# dual_switches.net
KiCad netlist of a schematic drawn in EAGLE
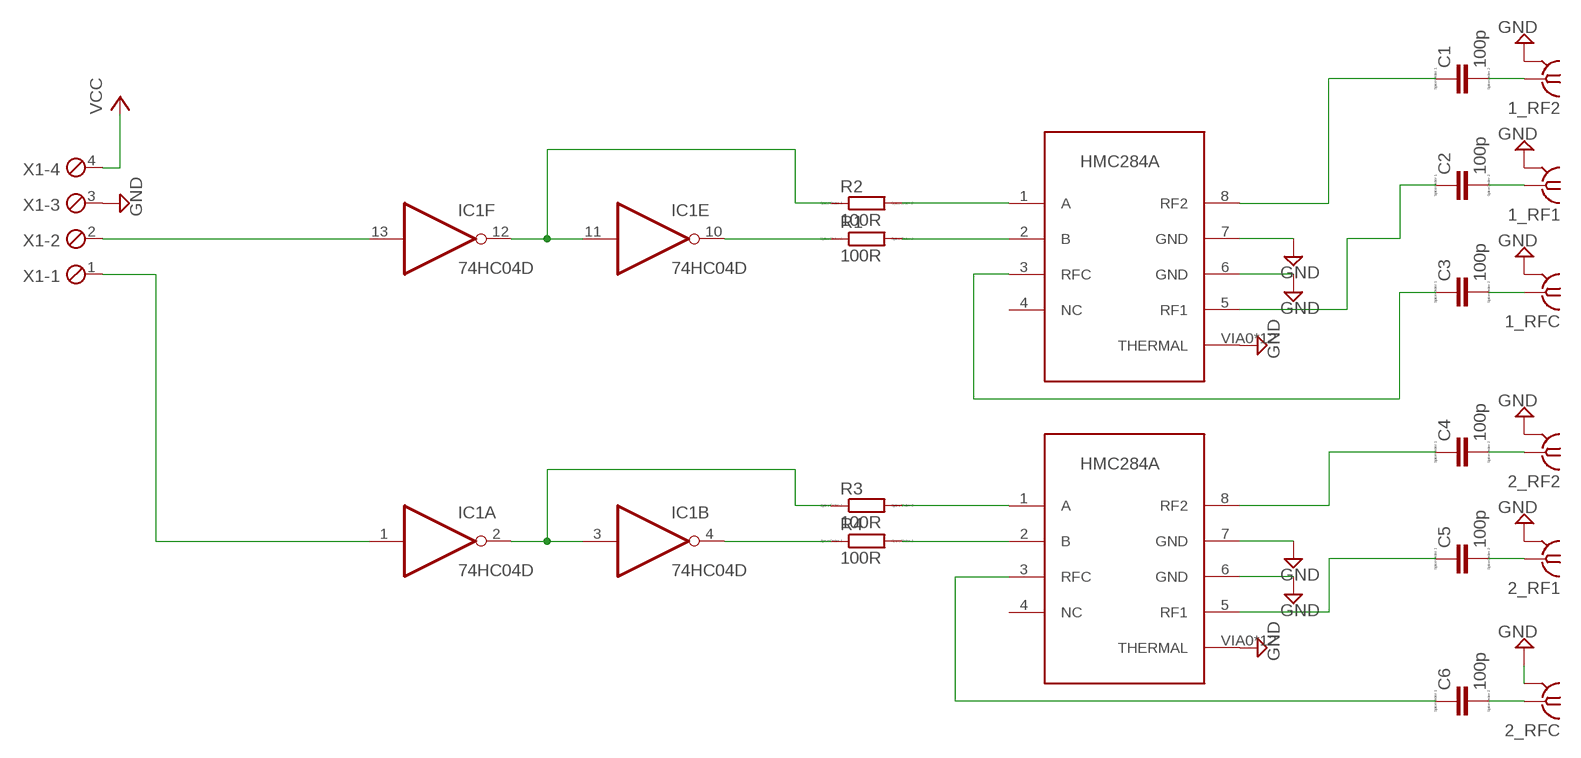
[diagram p0: schematic, sheet 1]

(export (version "E")
  (design (tool "Eeschema 10.0.6"))
  (components
    (comp (ref "1_RF1")
      (value "SMA-142-0701-801/806")
      (footprint "eagle-import:J502-ND-142-0701-801_806")
      (fields (field (name "MF") "JOHNSON COMPONENTS") (field (name "MPN") "142-0701-801"))
      (libsource (lib "eagle-import") (part "SMA-142-0701-801/806"))
    )
    (comp (ref "1_RF2")
      (value "SMA-142-0701-801/806")
      (footprint "eagle-import:J502-ND-142-0701-801_806")
      (fields (field (name "MF") "JOHNSON COMPONENTS") (field (name "MPN") "142-0701-801"))
      (libsource (lib "eagle-import") (part "SMA-142-0701-801/806"))
    )
    (comp (ref "1_RFC")
      (value "SMA-142-0701-801/806")
      (footprint "eagle-import:J502-ND-142-0701-801_806")
      (fields (field (name "MF") "JOHNSON COMPONENTS") (field (name "MPN") "142-0701-801"))
      (libsource (lib "eagle-import") (part "SMA-142-0701-801/806"))
    )
    (comp (ref "2_RF1")
      (value "SMA-142-0701-801/806")
      (footprint "eagle-import:J502-ND-142-0701-801_806")
      (fields (field (name "MF") "JOHNSON COMPONENTS") (field (name "MPN") "142-0701-801"))
      (libsource (lib "eagle-import") (part "SMA-142-0701-801/806"))
    )
    (comp (ref "2_RF2")
      (value "SMA-142-0701-801/806")
      (footprint "eagle-import:J502-ND-142-0701-801_806")
      (fields (field (name "MF") "JOHNSON COMPONENTS") (field (name "MPN") "142-0701-801"))
      (libsource (lib "eagle-import") (part "SMA-142-0701-801/806"))
    )
    (comp (ref "2_RFC")
      (value "SMA-142-0701-801/806")
      (footprint "eagle-import:J502-ND-142-0701-801_806")
      (fields (field (name "MF") "JOHNSON COMPONENTS") (field (name "MPN") "142-0701-801"))
      (libsource (lib "eagle-import") (part "SMA-142-0701-801/806"))
    )
    (comp (ref "C1")
      (value "100p")
      (footprint "eagle-import:C0402")
      (libsource (lib "eagle-import") (part "CC0402"))
    )
    (comp (ref "C2")
      (value "100p")
      (footprint "eagle-import:C0402")
      (libsource (lib "eagle-import") (part "CC0402"))
    )
    (comp (ref "C3")
      (value "100p")
      (footprint "eagle-import:C0402")
      (libsource (lib "eagle-import") (part "CC0402"))
    )
    (comp (ref "C4")
      (value "100p")
      (footprint "eagle-import:C0402")
      (libsource (lib "eagle-import") (part "CC0402"))
    )
    (comp (ref "C5")
      (value "100p")
      (footprint "eagle-import:C0402")
      (libsource (lib "eagle-import") (part "CC0402"))
    )
    (comp (ref "C6")
      (value "100p")
      (footprint "eagle-import:C0402")
      (libsource (lib "eagle-import") (part "CC0402"))
    )
    (comp (ref "IC1")
      (value "74HC04D")
      (footprint "eagle-import:SO14")
      (libsource (lib "eagle-import") (part "7404DHC"))
    )
    (comp (ref "R1")
      (value "100R")
      (footprint "eagle-import:R0603")
      (libsource (lib "eagle-import") (part "RR0603"))
    )
    (comp (ref "R2")
      (value "100R")
      (footprint "eagle-import:R0603")
      (libsource (lib "eagle-import") (part "RR0603"))
    )
    (comp (ref "R3")
      (value "100R")
      (footprint "eagle-import:R0603")
      (libsource (lib "eagle-import") (part "RR0603"))
    )
    (comp (ref "R4")
      (value "100R")
      (footprint "eagle-import:R0603")
      (libsource (lib "eagle-import") (part "RR0603"))
    )
    (comp (ref "U$1")
      (value "HMC284A")
      (footprint "eagle-import:MSOP-8G")
      (libsource (lib "eagle-import") (part "HMC284A"))
    )
    (comp (ref "U$2")
      (value "HMC284A")
      (footprint "eagle-import:MSOP-8G")
      (libsource (lib "eagle-import") (part "HMC284A"))
    )
    (comp (ref "X1")
      (value "MPT4")
      (footprint "eagle-import:4POL254")
      (libsource (lib "eagle-import") (part "MPT4"))
    )
  )
  (nets
    (net (code "1") (name "GND") (class "Default")
      (node (ref "1_RF1") (pin "G@1") (pinfunction "2_G@1") (pintype "passive"))
      (node (ref "1_RF1") (pin "G@2") (pinfunction "2_G@2") (pintype "passive"))
      (node (ref "1_RF1") (pin "G@3") (pinfunction "2_G@3") (pintype "passive"))
      (node (ref "1_RF1") (pin "G@4") (pinfunction "2_G@4") (pintype "passive"))
      (node (ref "1_RF2") (pin "G@1") (pinfunction "2_G@1") (pintype "passive"))
      (node (ref "1_RF2") (pin "G@2") (pinfunction "2_G@2") (pintype "passive"))
      (node (ref "1_RF2") (pin "G@3") (pinfunction "2_G@3") (pintype "passive"))
      (node (ref "1_RF2") (pin "G@4") (pinfunction "2_G@4") (pintype "passive"))
      (node (ref "1_RFC") (pin "G@1") (pinfunction "2_G@1") (pintype "passive"))
      (node (ref "1_RFC") (pin "G@2") (pinfunction "2_G@2") (pintype "passive"))
      (node (ref "1_RFC") (pin "G@3") (pinfunction "2_G@3") (pintype "passive"))
      (node (ref "1_RFC") (pin "G@4") (pinfunction "2_G@4") (pintype "passive"))
      (node (ref "2_RF1") (pin "G@1") (pinfunction "2_G@1") (pintype "passive"))
      (node (ref "2_RF1") (pin "G@2") (pinfunction "2_G@2") (pintype "passive"))
      (node (ref "2_RF1") (pin "G@3") (pinfunction "2_G@3") (pintype "passive"))
      (node (ref "2_RF1") (pin "G@4") (pinfunction "2_G@4") (pintype "passive"))
      (node (ref "2_RF2") (pin "G@1") (pinfunction "2_G@1") (pintype "passive"))
      (node (ref "2_RF2") (pin "G@2") (pinfunction "2_G@2") (pintype "passive"))
      (node (ref "2_RF2") (pin "G@3") (pinfunction "2_G@3") (pintype "passive"))
      (node (ref "2_RF2") (pin "G@4") (pinfunction "2_G@4") (pintype "passive"))
      (node (ref "2_RFC") (pin "G@1") (pinfunction "2_G@1") (pintype "passive"))
      (node (ref "2_RFC") (pin "G@2") (pinfunction "2_G@2") (pintype "passive"))
      (node (ref "2_RFC") (pin "G@3") (pinfunction "2_G@3") (pintype "passive"))
      (node (ref "2_RFC") (pin "G@4") (pinfunction "2_G@4") (pintype "passive"))
      (node (ref "U$1") (pin "6") (pinfunction "GND_6") (pintype "power_in"))
      (node (ref "U$1") (pin "7") (pinfunction "GND_7") (pintype "power_in"))
      (node (ref "U$1") (pin "VIA0") (pinfunction "THERMAL_VIA0") (pintype "power_in"))
      (node (ref "U$1") (pin "VIA1") (pinfunction "THERMAL_VIA1") (pintype "power_in"))
      (node (ref "U$1") (pin "VIA10") (pinfunction "THERMAL_VIA10") (pintype "power_in"))
      (node (ref "U$1") (pin "VIA11") (pinfunction "THERMAL_VIA11") (pintype "power_in"))
      (node (ref "U$1") (pin "VIA12") (pinfunction "THERMAL_VIA12") (pintype "power_in"))
      (node (ref "U$1") (pin "VIA2") (pinfunction "THERMAL_VIA2") (pintype "power_in"))
      (node (ref "U$1") (pin "VIA3") (pinfunction "THERMAL_VIA3") (pintype "power_in"))
      (node (ref "U$1") (pin "VIA5") (pinfunction "THERMAL_VIA5") (pintype "power_in"))
      (node (ref "U$1") (pin "VIA6") (pinfunction "THERMAL_VIA6") (pintype "power_in"))
      (node (ref "U$1") (pin "VIA7") (pinfunction "THERMAL_VIA7") (pintype "power_in"))
      (node (ref "U$1") (pin "VIA8") (pinfunction "THERMAL_VIA8") (pintype "power_in"))
      (node (ref "U$1") (pin "VIA9") (pinfunction "THERMAL_VIA9") (pintype "power_in"))
      (node (ref "U$2") (pin "6") (pinfunction "GND_6") (pintype "power_in"))
      (node (ref "U$2") (pin "7") (pinfunction "GND_7") (pintype "power_in"))
      (node (ref "U$2") (pin "VIA0") (pinfunction "THERMAL_VIA0") (pintype "power_in"))
      (node (ref "U$2") (pin "VIA1") (pinfunction "THERMAL_VIA1") (pintype "power_in"))
      (node (ref "U$2") (pin "VIA10") (pinfunction "THERMAL_VIA10") (pintype "power_in"))
      (node (ref "U$2") (pin "VIA11") (pinfunction "THERMAL_VIA11") (pintype "power_in"))
      (node (ref "U$2") (pin "VIA12") (pinfunction "THERMAL_VIA12") (pintype "power_in"))
      (node (ref "U$2") (pin "VIA2") (pinfunction "THERMAL_VIA2") (pintype "power_in"))
      (node (ref "U$2") (pin "VIA3") (pinfunction "THERMAL_VIA3") (pintype "power_in"))
      (node (ref "U$2") (pin "VIA5") (pinfunction "THERMAL_VIA5") (pintype "power_in"))
      (node (ref "U$2") (pin "VIA6") (pinfunction "THERMAL_VIA6") (pintype "power_in"))
      (node (ref "U$2") (pin "VIA7") (pinfunction "THERMAL_VIA7") (pintype "power_in"))
      (node (ref "U$2") (pin "VIA8") (pinfunction "THERMAL_VIA8") (pintype "power_in"))
      (node (ref "U$2") (pin "VIA9") (pinfunction "THERMAL_VIA9") (pintype "power_in"))
      (node (ref "X1") (pin "3") (pinfunction "1_3") (pintype "passive"))
    )
    (net (code "2") (name "Net-(1_RF1-Pad1)") (class "Default")
      (node (ref "1_RF1") (pin "1") (pinfunction "1_1") (pintype "passive"))
      (node (ref "C2") (pin "2") (pinfunction "2_2") (pintype "passive"))
    )
    (net (code "3") (name "Net-(1_RF2-Pad1)") (class "Default")
      (node (ref "1_RF2") (pin "1") (pinfunction "1_1") (pintype "passive"))
      (node (ref "C1") (pin "2") (pinfunction "2_2") (pintype "passive"))
    )
    (net (code "4") (name "Net-(1_RFC-Pad1)") (class "Default")
      (node (ref "1_RFC") (pin "1") (pinfunction "1_1") (pintype "passive"))
      (node (ref "C3") (pin "2") (pinfunction "2_2") (pintype "passive"))
    )
    (net (code "5") (name "Net-(2_RF1-Pad1)") (class "Default")
      (node (ref "2_RF1") (pin "1") (pinfunction "1_1") (pintype "passive"))
      (node (ref "C5") (pin "2") (pinfunction "2_2") (pintype "passive"))
    )
    (net (code "6") (name "Net-(2_RF2-Pad1)") (class "Default")
      (node (ref "2_RF2") (pin "1") (pinfunction "1_1") (pintype "passive"))
      (node (ref "C4") (pin "2") (pinfunction "2_2") (pintype "passive"))
    )
    (net (code "7") (name "Net-(2_RFC-Pad1)") (class "Default")
      (node (ref "2_RFC") (pin "1") (pinfunction "1_1") (pintype "passive"))
      (node (ref "C6") (pin "2") (pinfunction "2_2") (pintype "passive"))
    )
    (net (code "8") (name "Net-(IC1A-I)") (class "Default")
      (node (ref "IC1") (pin "1") (pinfunction "I_1") (pintype "input"))
      (node (ref "X1") (pin "1") (pinfunction "1_1") (pintype "passive"))
    )
    (net (code "9") (name "Net-(IC1A-O)") (class "Default")
      (node (ref "IC1") (pin "2") (pinfunction "O_2") (pintype "output"))
      (node (ref "IC1") (pin "3") (pinfunction "I_3") (pintype "input"))
      (node (ref "R3") (pin "1") (pinfunction "1_1") (pintype "passive"))
    )
    (net (code "10") (name "Net-(IC1B-O)") (class "Default")
      (node (ref "IC1") (pin "4") (pinfunction "O_4") (pintype "output"))
      (node (ref "R4") (pin "1") (pinfunction "1_1") (pintype "passive"))
    )
    (net (code "11") (name "Net-(IC1E-I)") (class "Default")
      (node (ref "IC1") (pin "11") (pinfunction "I_11") (pintype "input"))
      (node (ref "IC1") (pin "12") (pinfunction "O_12") (pintype "output"))
      (node (ref "R2") (pin "1") (pinfunction "1_1") (pintype "passive"))
    )
    (net (code "12") (name "Net-(IC1E-O)") (class "Default")
      (node (ref "IC1") (pin "10") (pinfunction "O_10") (pintype "output"))
      (node (ref "R1") (pin "1") (pinfunction "1_1") (pintype "passive"))
    )
    (net (code "13") (name "Net-(IC1F-I)") (class "Default")
      (node (ref "IC1") (pin "13") (pinfunction "I_13") (pintype "input"))
      (node (ref "X1") (pin "2") (pinfunction "1_2") (pintype "passive"))
    )
    (net (code "14") (name "Net-(U$1-A)") (class "Default")
      (node (ref "R2") (pin "2") (pinfunction "2_2") (pintype "passive"))
      (node (ref "U$1") (pin "1") (pinfunction "A_1") (pintype "input"))
    )
    (net (code "15") (name "Net-(U$1-B)") (class "Default")
      (node (ref "R1") (pin "2") (pinfunction "2_2") (pintype "passive"))
      (node (ref "U$1") (pin "2") (pinfunction "B_2") (pintype "input"))
    )
    (net (code "16") (name "Net-(U$1-RF1)") (class "Default")
      (node (ref "C2") (pin "1") (pinfunction "1_1") (pintype "passive"))
      (node (ref "U$1") (pin "5") (pinfunction "RF1_5") (pintype "bidirectional"))
    )
    (net (code "17") (name "Net-(U$1-RF2)") (class "Default")
      (node (ref "C1") (pin "1") (pinfunction "1_1") (pintype "passive"))
      (node (ref "U$1") (pin "8") (pinfunction "RF2_8") (pintype "bidirectional"))
    )
    (net (code "18") (name "Net-(U$1-RFC)") (class "Default")
      (node (ref "C3") (pin "1") (pinfunction "1_1") (pintype "passive"))
      (node (ref "U$1") (pin "3") (pinfunction "RFC_3") (pintype "output"))
    )
    (net (code "19") (name "Net-(U$2-A)") (class "Default")
      (node (ref "R3") (pin "2") (pinfunction "2_2") (pintype "passive"))
      (node (ref "U$2") (pin "1") (pinfunction "A_1") (pintype "input"))
    )
    (net (code "20") (name "Net-(U$2-B)") (class "Default")
      (node (ref "R4") (pin "2") (pinfunction "2_2") (pintype "passive"))
      (node (ref "U$2") (pin "2") (pinfunction "B_2") (pintype "input"))
    )
    (net (code "21") (name "Net-(U$2-RF1)") (class "Default")
      (node (ref "C5") (pin "1") (pinfunction "1_1") (pintype "passive"))
      (node (ref "U$2") (pin "5") (pinfunction "RF1_5") (pintype "bidirectional"))
    )
    (net (code "22") (name "Net-(U$2-RF2)") (class "Default")
      (node (ref "C4") (pin "1") (pinfunction "1_1") (pintype "passive"))
      (node (ref "U$2") (pin "8") (pinfunction "RF2_8") (pintype "bidirectional"))
    )
    (net (code "23") (name "Net-(U$2-RFC)") (class "Default")
      (node (ref "C6") (pin "1") (pinfunction "1_1") (pintype "passive"))
      (node (ref "U$2") (pin "3") (pinfunction "RFC_3") (pintype "output"))
    )
    (net (code "24") (name "VCC") (class "Default")
      (node (ref "X1") (pin "4") (pinfunction "1_4") (pintype "passive"))
    )
    (net (code "25") (name "unconnected-(U$1-NC-Pad4)") (class "Default")
      (node (ref "U$1") (pin "4") (pinfunction "NC_4") (pintype "no_connect"))
    )
    (net (code "26") (name "unconnected-(U$2-NC-Pad4)") (class "Default")
      (node (ref "U$2") (pin "4") (pinfunction "NC_4") (pintype "no_connect"))
    )
  )
)
